# Assignment1.net
KiCad netlist of a schematic drawn in Altium Designer
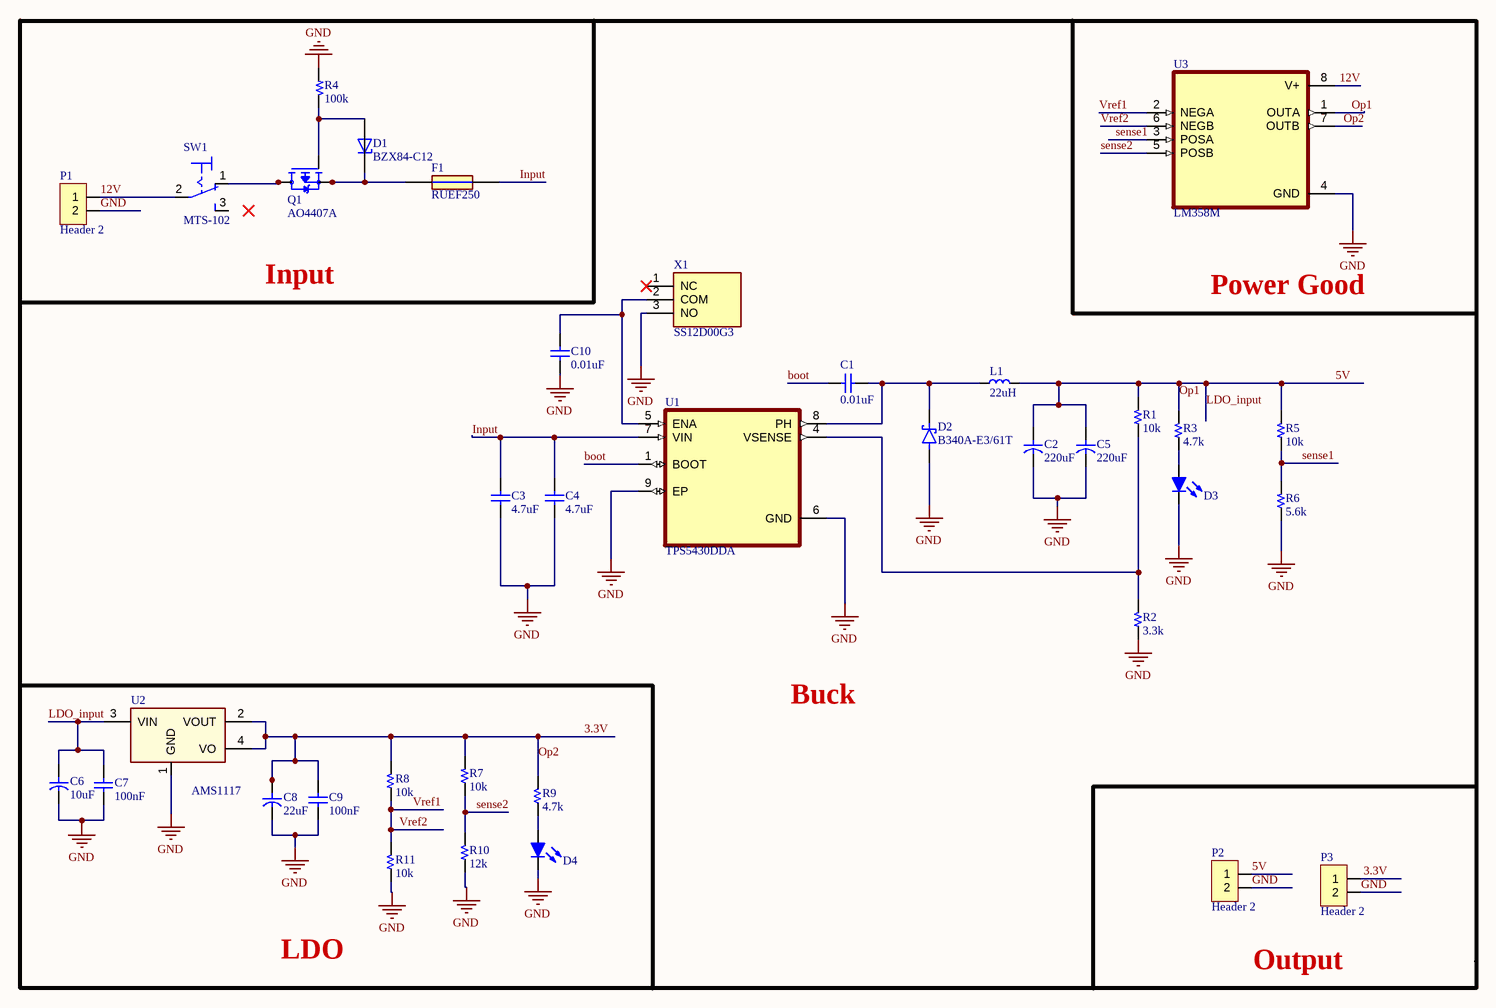
[diagram p0: Assignment1.SchDoc]

(export (version "E")
  (design (tool "Eeschema 10.0.6"))
  (components
    (comp (ref "C1")
      (value "0.01uF")
      (footprint "C 0805")
      (description "Capacitor non-pol")
      (libsource (lib "chipfc_libs") (part "Capacitor NP"))
    )
    (comp (ref "C2")
      (value "220uF")
      (footprint "C SMD TAN 2917 (E)")
      (description "Capacitor pol")
      (libsource (lib "chipfc_altium_libs") (part "Capacitor"))
    )
    (comp (ref "C3")
      (value "4.7uF")
      (footprint "C 0805")
      (description "Capacitor non-pol")
      (libsource (lib "chipfc_altium_libs") (part "Capacitor NP"))
    )
    (comp (ref "C4")
      (value "4.7uF")
      (footprint "C 0805")
      (description "Capacitor non-pol")
      (libsource (lib "chipfc_altium_libs") (part "Capacitor NP"))
    )
    (comp (ref "C5")
      (value "220uF")
      (footprint "C SMD TAN 2917 (E)")
      (description "Capacitor pol")
      (libsource (lib "chipfc_altium_libs") (part "Capacitor"))
    )
    (comp (ref "C6")
      (value "10uF")
      (footprint "C SMD ALU (B)")
      (description "Capacitor pol")
      (libsource (lib "chipfc_altium_libs") (part "Capacitor"))
    )
    (comp (ref "C7")
      (value "100nF")
      (footprint "C 0805")
      (description "Capacitor non-pol")
      (libsource (lib "chipfc_altium_libs") (part "Capacitor NP"))
    )
    (comp (ref "C8")
      (value "22uF")
      (footprint "C SMD TAN 2917 (E)")
      (description "Capacitor pol")
      (libsource (lib "chipfc_altium_libs") (part "Capacitor"))
    )
    (comp (ref "C9")
      (value "100nF")
      (footprint "C 0805")
      (description "Capacitor non-pol")
      (libsource (lib "chipfc_altium_libs") (part "Capacitor NP"))
    )
    (comp (ref "C10")
      (value "0.01uF")
      (footprint "C 0805")
      (description "Capacitor non-pol")
      (libsource (lib "chipfc_libs") (part "Capacitor NP"))
    )
    (comp (ref "D1")
      (value "BZX84-C12")
      (footprint "SOT95P230X110-3N")
      (description "Zener Diode 12 V 250 mW Â±5% Surface Mount TO-236AB")
      (fields (field (name "MF") "Nexperia USA"))
      (libsource (lib "BZX84-C12") (part "BZX84-C12"))
    )
    (comp (ref "D2")
      (value "B340A-E3/61T")
      (footprint "DIOM5126X229N")
      (description "Diode Schottky 40 V 3A Surface Mount DO-214AC (SMA)")
      (fields (field (name "MF") "Vishay Semiconductor"))
      (libsource (lib "B340A-E3_61T") (part "B340A-E3/61T"))
    )
    (comp (ref "D3")
      (value "Led")
      (footprint "LED 3MM - green")
      (description "Typical LED")
      (libsource (lib "chipfc_altium_libs") (part "Led"))
    )
    (comp (ref "D4")
      (value "Led")
      (footprint "LED 3MM - green")
      (description "Typical LED")
      (libsource (lib "chipfc_altium_libs") (part "Led"))
    )
    (comp (ref "F1")
      (value "RUEF250")
      (footprint "RUEF250")
      (description "Littelfuse 2.5A Radial Leaded PCB Mount Resettable Fuse, 30V dc")
      (fields (field (name "MOUSER PART NUMBER") "650-RUEF250"))
      (libsource (lib "RUEF250") (part "RUEF250"))
    )
    (comp (ref "L1")
      (value "22uH")
      (footprint "Inductor SMD 12x12x8")
      (description "Inductor")
      (libsource (lib "chipfc_altium_libs") (part "Inductor"))
    )
    (comp (ref "P1")
      (value "Header 2")
      (footprint "HDR/Terminal/2")
      (description "Header, 2-Pin")
      (libsource (lib "chipfc_altium_libs") (part "Header 2"))
    )
    (comp (ref "P2")
      (value "Header 2")
      (footprint "HDR/Terminal/2")
      (description "Header, 2-Pin")
      (libsource (lib "chipfc_altium_libs") (part "Header 2"))
    )
    (comp (ref "P3")
      (value "Header 2")
      (footprint "HDR/Terminal/2")
      (description "Header, 2-Pin")
      (libsource (lib "chipfc_altium_libs") (part "Header 2"))
    )
    (comp (ref "Q1")
      (value "AO4407A")
      (footprint "SOIC127P600X175-8N")
      (description "P-Channel 30 V 12A (Ta) 3.1W (Ta) Surface Mount 8-SOIC")
      (fields (field (name "MF") "Alpha &"))
      (libsource (lib "AO4407A") (part "AO4407A"))
    )
    (comp (ref "R1")
      (value "10k")
      (footprint "R 1206")
      (description "Resistor")
      (libsource (lib "chipfc_altium_libs") (part "Resistor"))
    )
    (comp (ref "R2")
      (value "3.3k")
      (footprint "R 1206")
      (description "Resistor")
      (libsource (lib "chipfc_altium_libs") (part "Resistor"))
    )
    (comp (ref "R3")
      (value "4.7k")
      (footprint "R 1206")
      (description "Resistor")
      (libsource (lib "chipfc_altium_libs") (part "Resistor"))
    )
    (comp (ref "R4")
      (value "100k")
      (footprint "R 1206")
      (description "Resistor")
      (libsource (lib "chipfc_altium_libs") (part "Resistor"))
    )
    (comp (ref "R5")
      (value "10k")
      (footprint "R 1206")
      (description "Resistor")
      (libsource (lib "chipfc_altium_libs") (part "Resistor"))
    )
    (comp (ref "R6")
      (value "5.6k")
      (footprint "R 1206")
      (description "Resistor")
      (libsource (lib "chipfc_altium_libs") (part "Resistor"))
    )
    (comp (ref "R7")
      (value "10k")
      (footprint "R 1206")
      (description "Resistor")
      (libsource (lib "chipfc_altium_libs") (part "Resistor"))
    )
    (comp (ref "R8")
      (value "10k")
      (footprint "R 1206")
      (description "Resistor")
      (libsource (lib "chipfc_altium_libs") (part "Resistor"))
    )
    (comp (ref "R9")
      (value "4.7k")
      (footprint "R 1206")
      (description "Resistor")
      (libsource (lib "chipfc_altium_libs") (part "Resistor"))
    )
    (comp (ref "R10")
      (value "12k")
      (footprint "R 1206")
      (description "Resistor")
      (libsource (lib "chipfc_altium_libs") (part "Resistor"))
    )
    (comp (ref "R11")
      (value "10k")
      (footprint "R 1206")
      (description "Resistor")
      (libsource (lib "chipfc_altium_libs") (part "Resistor"))
    )
    (comp (ref "SW1")
      (value "MTS-102")
      (footprint "MTS-102")
      (description "Rectangular Cable Assemblies .100 Mini Mate Single Row Discrete Wire Cable Assembly, Terminal")
      (fields (field (name "MF") "Motorola") (field (name "MP") "MTS102"))
      (libsource (lib "MTS-102") (part "MTS-102"))
    )
    (comp (ref "U1")
      (value "TPS5430DDA")
      (footprint "VREG_LM5017MR/NOPB")
      (description "5.5V to 36V Input, 3A, 500kHz Step-Down Converter")
      (fields (field (name "MF") "Texas Instruments"))
      (libsource (lib "TPS5430DDA") (part "TPS5430DDA"))
    )
    (comp (ref "U2")
      (value "AMS1117")
      (footprint "SOT-223")
      (description "1A LDO Voltage Regulator, ADJ or fixed 1.5/1.8/2.5/2.85/3.3/5V")
      (libsource (lib "chipfc_altium_libs") (part "AMS1117"))
    )
    (comp (ref "U3")
      (value "LM358M")
      (footprint "SOIC127P599X175-8N")
      (description "Op Amp Dual Low Power Amplifier Â±16V/32V 8-Pin SOIC Tube")
      (fields (field (name "MF") "onsemi"))
      (libsource (lib "LM358M") (part "LM358M"))
    )
    (comp (ref "X1")
      (value "SS12D00G3")
      (footprint "SS12D00G3")
      (description "3 Pin Toggle Switch")
      (libsource (lib "SS12D00G3") (part "SS12D00G3"))
    )
  )
  (nets
    (net (code "1") (name "/3.3V") (class "Default")
      (node (ref "C8") (pin "1") (pinfunction "1_1") (pintype "passive"))
      (node (ref "C9") (pin "1") (pinfunction "1_1") (pintype "passive"))
      (node (ref "P3") (pin "1") (pinfunction "1_1") (pintype "passive"))
      (node (ref "R7") (pin "2") (pinfunction "2_2") (pintype "passive"))
      (node (ref "R8") (pin "2") (pinfunction "2_2") (pintype "passive"))
      (node (ref "R9") (pin "2") (pinfunction "2_2") (pintype "passive"))
      (node (ref "U2") (pin "2") (pinfunction "VOUT_2") (pintype "passive"))
      (node (ref "U2") (pin "4") (pinfunction "VO_4") (pintype "passive"))
      (node (ref "U3") (pin "7") (pinfunction "OUTB_7") (pintype "output"))
    )
    (net (code "2") (name "/5V") (class "Default")
      (node (ref "C2") (pin "1") (pinfunction "1_1") (pintype "passive"))
      (node (ref "C5") (pin "1") (pinfunction "1_1") (pintype "passive"))
      (node (ref "C6") (pin "1") (pinfunction "1_1") (pintype "passive"))
      (node (ref "C7") (pin "1") (pinfunction "1_1") (pintype "passive"))
      (node (ref "L1") (pin "2") (pinfunction "2_2") (pintype "passive"))
      (node (ref "P2") (pin "1") (pinfunction "1_1") (pintype "passive"))
      (node (ref "R1") (pin "2") (pinfunction "2_2") (pintype "passive"))
      (node (ref "R3") (pin "2") (pinfunction "2_2") (pintype "passive"))
      (node (ref "R5") (pin "2") (pinfunction "2_2") (pintype "passive"))
      (node (ref "U2") (pin "3") (pinfunction "VIN_3") (pintype "power_in"))
      (node (ref "U3") (pin "1") (pinfunction "OUTA_1") (pintype "output"))
    )
    (net (code "3") (name "/12V") (class "Default")
      (node (ref "P1") (pin "1") (pinfunction "1_1") (pintype "passive"))
      (node (ref "SW1") (pin "2") (pinfunction "P_2") (pintype "passive"))
      (node (ref "U3") (pin "8") (pinfunction "V+_8") (pintype "power_in"))
    )
    (net (code "4") (name "/Input") (class "Default")
      (node (ref "C3") (pin "1") (pinfunction "1_1") (pintype "passive"))
      (node (ref "C4") (pin "1") (pinfunction "1_1") (pintype "passive"))
      (node (ref "F1") (pin "2") (pinfunction "2_2") (pintype "passive"))
      (node (ref "U1") (pin "7") (pinfunction "VIN_7") (pintype "input"))
    )
    (net (code "5") (name "/Vref1") (class "Default")
      (node (ref "R11") (pin "2") (pinfunction "2_2") (pintype "passive"))
      (node (ref "R8") (pin "1") (pinfunction "1_1") (pintype "passive"))
      (node (ref "U3") (pin "2") (pinfunction "NEGA_2") (pintype "input"))
      (node (ref "U3") (pin "6") (pinfunction "NEGB_6") (pintype "input"))
    )
    (net (code "6") (name "/boot") (class "Default")
      (node (ref "C1") (pin "1") (pinfunction "1_1") (pintype "passive"))
      (node (ref "U1") (pin "1") (pinfunction "BOOT_1") (pintype "bidirectional"))
    )
    (net (code "7") (name "/sense1") (class "Default")
      (node (ref "R5") (pin "1") (pinfunction "1_1") (pintype "passive"))
      (node (ref "R6") (pin "2") (pinfunction "2_2") (pintype "passive"))
      (node (ref "U3") (pin "3") (pinfunction "POSA_3") (pintype "input"))
    )
    (net (code "8") (name "/sense2") (class "Default")
      (node (ref "R10") (pin "2") (pinfunction "2_2") (pintype "passive"))
      (node (ref "R7") (pin "1") (pinfunction "1_1") (pintype "passive"))
      (node (ref "U3") (pin "5") (pinfunction "POSB_5") (pintype "input"))
    )
    (net (code "9") (name "GND") (class "Default")
      (node (ref "C10") (pin "1") (pinfunction "1_1") (pintype "passive"))
      (node (ref "C2") (pin "2") (pinfunction "2_2") (pintype "passive"))
      (node (ref "C3") (pin "2") (pinfunction "2_2") (pintype "passive"))
      (node (ref "C4") (pin "2") (pinfunction "2_2") (pintype "passive"))
      (node (ref "C5") (pin "2") (pinfunction "2_2") (pintype "passive"))
      (node (ref "C6") (pin "2") (pinfunction "2_2") (pintype "passive"))
      (node (ref "C7") (pin "2") (pinfunction "2_2") (pintype "passive"))
      (node (ref "C8") (pin "2") (pinfunction "2_2") (pintype "passive"))
      (node (ref "C9") (pin "2") (pinfunction "2_2") (pintype "passive"))
      (node (ref "D2") (pin "A") (pinfunction "A_A") (pintype "passive"))
      (node (ref "D3") (pin "2") (pinfunction "K_2") (pintype "passive"))
      (node (ref "D4") (pin "2") (pinfunction "K_2") (pintype "passive"))
      (node (ref "P1") (pin "2") (pinfunction "2_2") (pintype "passive"))
      (node (ref "P2") (pin "2") (pinfunction "2_2") (pintype "passive"))
      (node (ref "P3") (pin "2") (pinfunction "2_2") (pintype "passive"))
      (node (ref "R10") (pin "1") (pinfunction "1_1") (pintype "passive"))
      (node (ref "R11") (pin "1") (pinfunction "1_1") (pintype "passive"))
      (node (ref "R2") (pin "1") (pinfunction "1_1") (pintype "passive"))
      (node (ref "R4") (pin "1") (pinfunction "1_1") (pintype "passive"))
      (node (ref "R6") (pin "1") (pinfunction "1_1") (pintype "passive"))
      (node (ref "U1") (pin "6") (pinfunction "GND_6") (pintype "power_in"))
      (node (ref "U1") (pin "9") (pinfunction "EP_9") (pintype "bidirectional"))
      (node (ref "U2") (pin "1") (pinfunction "GND_1") (pintype "passive"))
      (node (ref "U3") (pin "4") (pinfunction "GND_4") (pintype "power_in"))
      (node (ref "X1") (pin "3") (pinfunction "NO_3") (pintype "passive"))
    )
    (net (code "10") (name "Net-(D1-A)") (class "Default")
      (node (ref "D1") (pin "1") (pinfunction "A_1") (pintype "passive"))
      (node (ref "Q1") (pin "4") (pinfunction "G_4") (pintype "passive"))
      (node (ref "R4") (pin "2") (pinfunction "2_2") (pintype "passive"))
    )
    (net (code "11") (name "Net-(D1-C)") (class "Default")
      (node (ref "D1") (pin "3") (pinfunction "C_3") (pintype "passive"))
      (node (ref "F1") (pin "1") (pinfunction "1_1") (pintype "passive"))
      (node (ref "Q1") (pin "1") (pinfunction "S_1") (pintype "passive"))
      (node (ref "Q1") (pin "2") (pinfunction "S_2") (pintype "passive"))
      (node (ref "Q1") (pin "3") (pinfunction "S_3") (pintype "passive"))
    )
    (net (code "12") (name "Net-(D3-A)") (class "Default")
      (node (ref "D3") (pin "1") (pinfunction "A_1") (pintype "passive"))
      (node (ref "R3") (pin "1") (pinfunction "1_1") (pintype "passive"))
    )
    (net (code "13") (name "Net-(D4-A)") (class "Default")
      (node (ref "D4") (pin "1") (pinfunction "A_1") (pintype "passive"))
      (node (ref "R9") (pin "1") (pinfunction "1_1") (pintype "passive"))
    )
    (net (code "14") (name "Net-(SW1-O)") (class "Default")
      (node (ref "Q1") (pin "5") (pinfunction "D_5") (pintype "passive"))
      (node (ref "Q1") (pin "6") (pinfunction "D_6") (pintype "passive"))
      (node (ref "Q1") (pin "7") (pinfunction "D_7") (pintype "passive"))
      (node (ref "Q1") (pin "8") (pinfunction "D_8") (pintype "passive"))
      (node (ref "SW1") (pin "1") (pinfunction "O_1") (pintype "passive"))
    )
    (net (code "15") (name "Net-(U1-ENA)") (class "Default")
      (node (ref "C10") (pin "2") (pinfunction "2_2") (pintype "passive"))
      (node (ref "U1") (pin "5") (pinfunction "ENA_5") (pintype "input"))
      (node (ref "X1") (pin "2") (pinfunction "COM_2") (pintype "passive"))
    )
    (net (code "16") (name "Net-(U1-PH)") (class "Default")
      (node (ref "C1") (pin "2") (pinfunction "2_2") (pintype "passive"))
      (node (ref "D2") (pin "C") (pinfunction "C_C") (pintype "passive"))
      (node (ref "L1") (pin "1") (pinfunction "1_1") (pintype "passive"))
      (node (ref "U1") (pin "8") (pinfunction "PH_8") (pintype "output"))
    )
    (net (code "17") (name "Net-(U1-VSENSE)") (class "Default")
      (node (ref "R1") (pin "1") (pinfunction "1_1") (pintype "passive"))
      (node (ref "R2") (pin "2") (pinfunction "2_2") (pintype "passive"))
      (node (ref "U1") (pin "4") (pinfunction "VSENSE_4") (pintype "output"))
    )
    (net (code "18") (name "unconnected-(SW1-S-Pad3)") (class "Default")
      (node (ref "SW1") (pin "3") (pinfunction "S_3") (pintype "passive"))
    )
    (net (code "19") (name "unconnected-(X1-NC-Pad1)") (class "Default")
      (node (ref "X1") (pin "1") (pinfunction "NC_1") (pintype "passive+no_connect"))
    )
  )
)
